# eMMC.net
KiCad netlist of a schematic drawn in Altium Designer
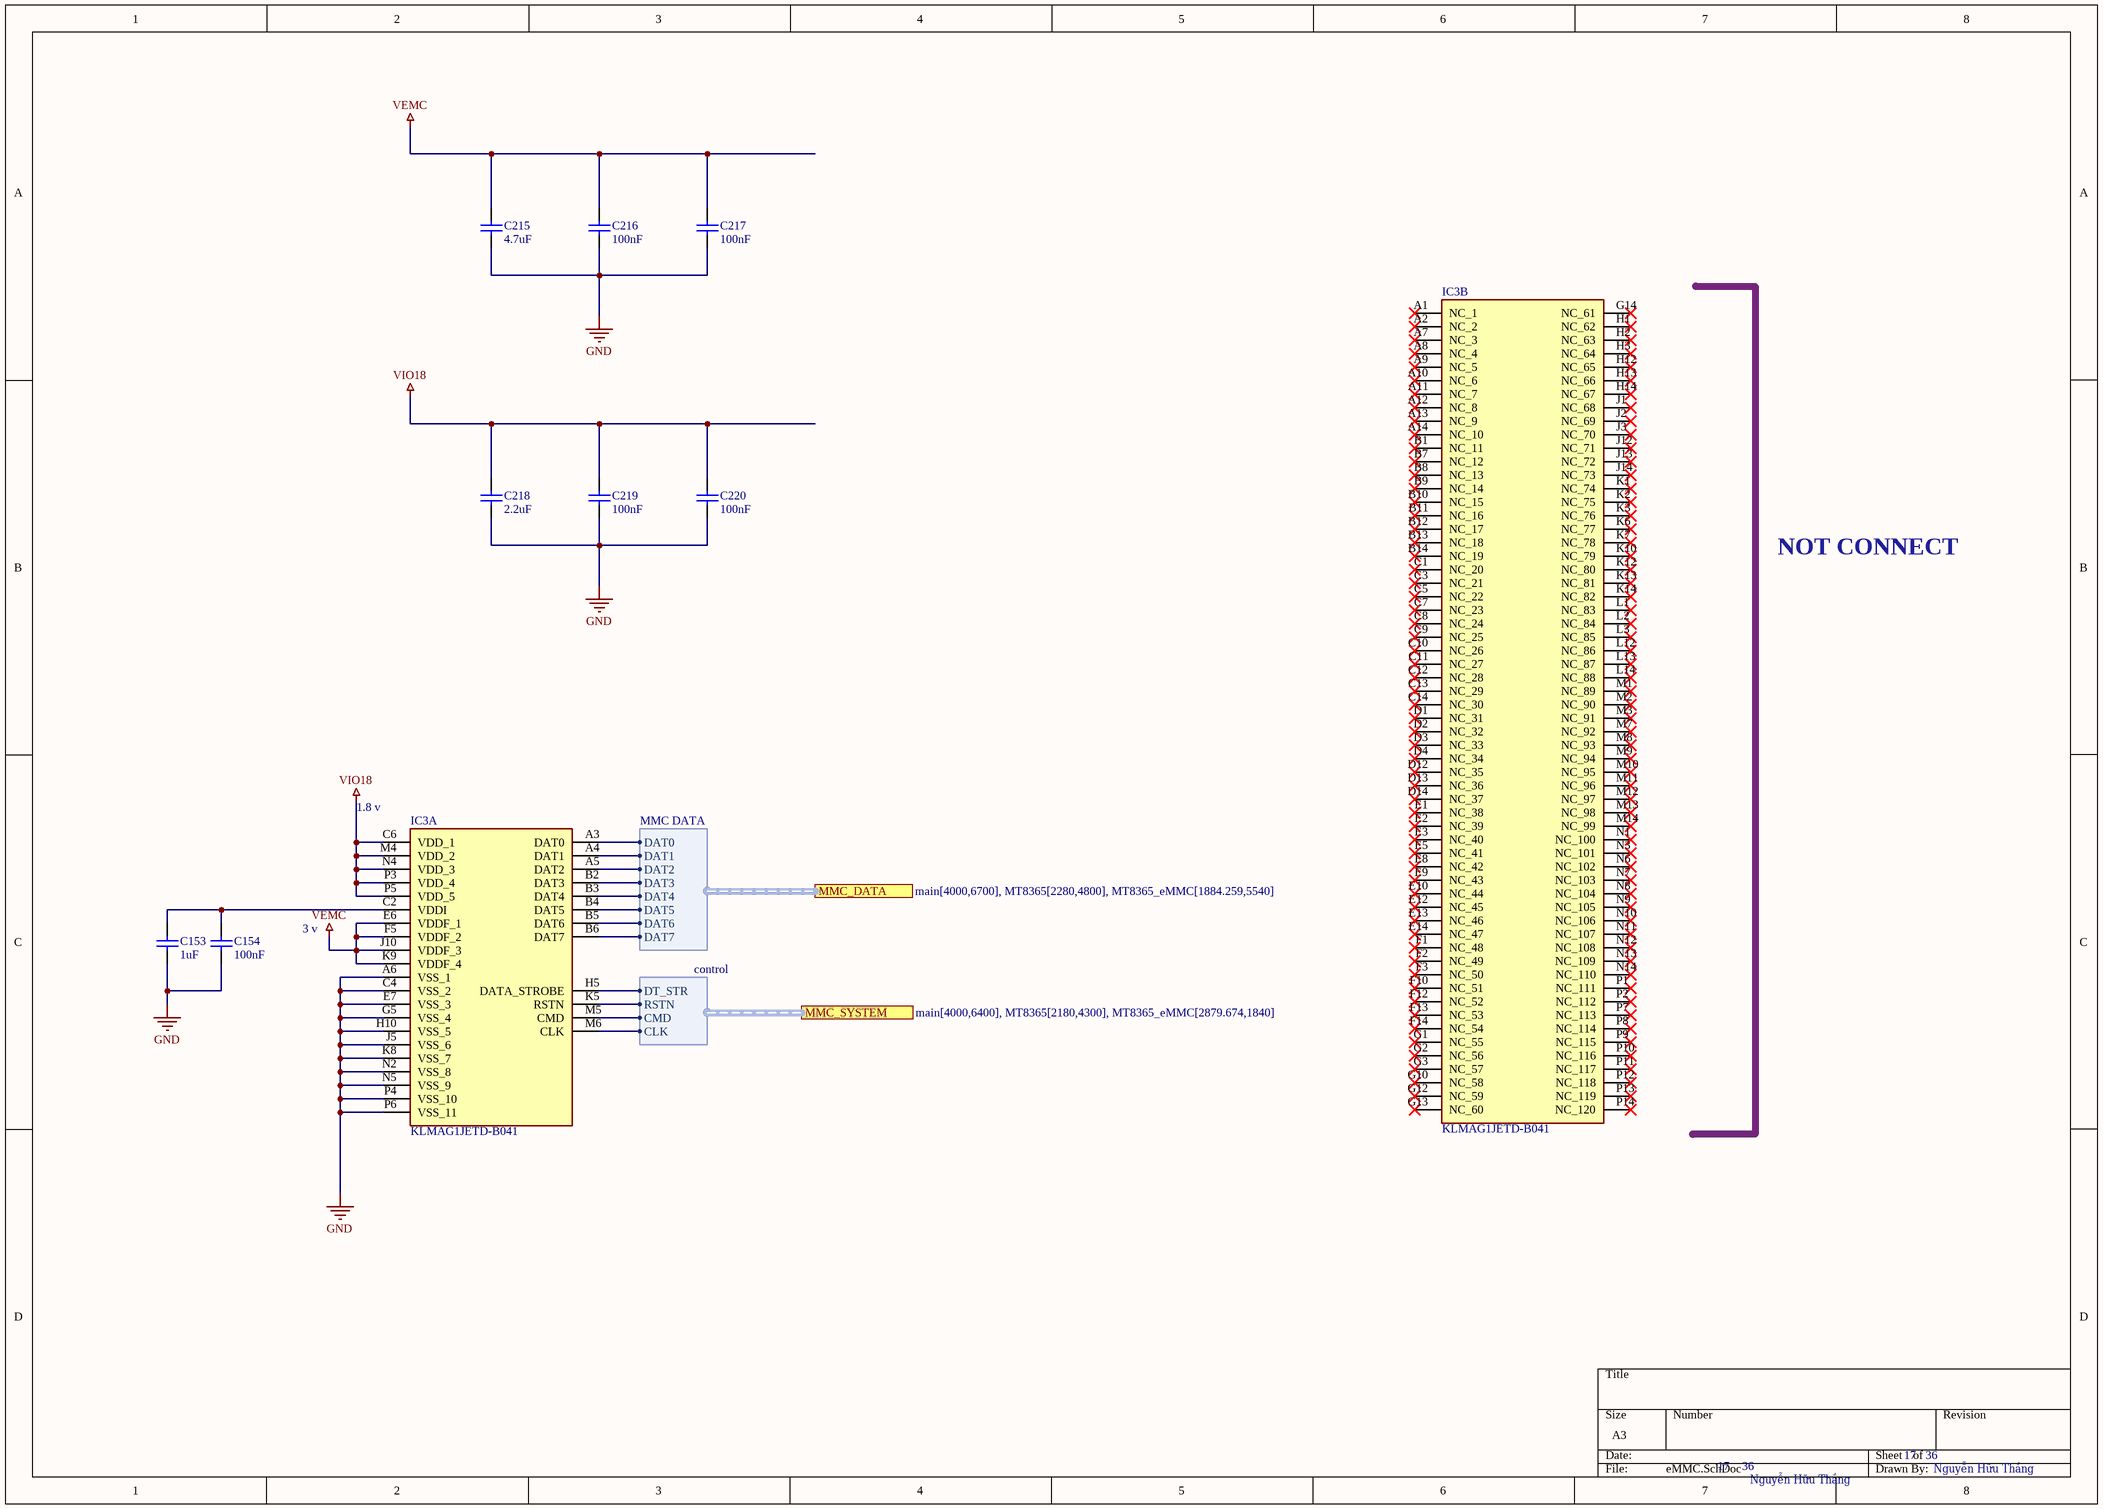
[diagram p0: eMMC.SchDoc]

(export (version "E")
  (design (tool "Eeschema 10.0.6"))
  (components
    (comp (ref "C153")
      (value "1uF")
      (footprint "C0805")
      (fields (field (name "Comment") "C0805"))
      (libsource (lib "kit") (part "C0805"))
    )
    (comp (ref "C154")
      (value "100nF")
      (footprint "C0603")
      (fields (field (name "Comment") "C0603"))
      (libsource (lib "kit") (part "C0603"))
    )
    (comp (ref "C215")
      (value "4.7uF")
      (footprint "C0805")
      (fields (field (name "Comment") "C0805"))
      (libsource (lib "kit") (part "C0805"))
    )
    (comp (ref "C216")
      (value "100nF")
      (footprint "C0603")
      (fields (field (name "Comment") "C0603"))
      (libsource (lib "kit") (part "C0603"))
    )
    (comp (ref "C217")
      (value "100nF")
      (footprint "C0603")
      (fields (field (name "Comment") "C0603"))
      (libsource (lib "kit") (part "C0603"))
    )
    (comp (ref "C218")
      (value "2.2uF")
      (footprint "C0805")
      (fields (field (name "Comment") "C0805"))
      (libsource (lib "kit") (part "C0805"))
    )
    (comp (ref "C219")
      (value "100nF")
      (footprint "C0603")
      (fields (field (name "Comment") "C0603"))
      (libsource (lib "kit") (part "C0603"))
    )
    (comp (ref "C220")
      (value "100nF")
      (footprint "C0603")
      (fields (field (name "Comment") "C0603"))
      (libsource (lib "kit") (part "C0603"))
    )
    (comp (ref "IC3")
      (value "KLMAG1JETD-B041")
      (footprint "BGA153C50P14X14_1150X1300X80")
      (description "Integrated Circuit")
      (libsource (lib "") (part "KLMAG1JETD-B041_1"))
    )
  )
  (nets
    (net (code "4") (name "/CLK") (class "Default")
      (node (ref "IC3") (pin "M6") (pinfunction "CLK_M6") (pintype "passive"))
    )
    (net (code "5") (name "/CMD") (class "Default")
      (node (ref "IC3") (pin "M5") (pinfunction "CMD_M5") (pintype "passive"))
    )
    (net (code "6") (name "/DAT0") (class "Default")
      (node (ref "IC3") (pin "A3") (pinfunction "DAT0_A3") (pintype "passive"))
    )
    (net (code "7") (name "/DAT1") (class "Default")
      (node (ref "IC3") (pin "A4") (pinfunction "DAT1_A4") (pintype "passive"))
    )
    (net (code "8") (name "/DAT2") (class "Default")
      (node (ref "IC3") (pin "A5") (pinfunction "DAT2_A5") (pintype "passive"))
    )
    (net (code "9") (name "/DAT3") (class "Default")
      (node (ref "IC3") (pin "B2") (pinfunction "DAT3_B2") (pintype "passive"))
    )
    (net (code "10") (name "/DAT4") (class "Default")
      (node (ref "IC3") (pin "B3") (pinfunction "DAT4_B3") (pintype "passive"))
    )
    (net (code "11") (name "/DAT5") (class "Default")
      (node (ref "IC3") (pin "B4") (pinfunction "DAT5_B4") (pintype "passive"))
    )
    (net (code "12") (name "/DAT6") (class "Default")
      (node (ref "IC3") (pin "B5") (pinfunction "DAT6_B5") (pintype "passive"))
    )
    (net (code "13") (name "/DAT7") (class "Default")
      (node (ref "IC3") (pin "B6") (pinfunction "DAT7_B6") (pintype "passive"))
    )
    (net (code "14") (name "/DT_STR") (class "Default")
      (node (ref "IC3") (pin "H5") (pinfunction "DATA_STROBE_H5") (pintype "passive"))
    )
    (net (code "15") (name "/RSTN") (class "Default")
      (node (ref "IC3") (pin "K5") (pinfunction "RSTN_K5") (pintype "passive"))
    )
    (net (code "18") (name "GND") (class "Default")
      (node (ref "C153") (pin "1") (pinfunction "1_1") (pintype "passive"))
      (node (ref "C154") (pin "1") (pinfunction "1_1") (pintype "passive"))
      (node (ref "C215") (pin "1") (pinfunction "1_1") (pintype "passive"))
      (node (ref "C216") (pin "1") (pinfunction "1_1") (pintype "passive"))
      (node (ref "C217") (pin "1") (pinfunction "1_1") (pintype "passive"))
      (node (ref "C218") (pin "1") (pinfunction "1_1") (pintype "passive"))
      (node (ref "C219") (pin "1") (pinfunction "1_1") (pintype "passive"))
      (node (ref "C220") (pin "1") (pinfunction "1_1") (pintype "passive"))
      (node (ref "IC3") (pin "A6") (pinfunction "VSS_1_A6") (pintype "passive"))
      (node (ref "IC3") (pin "C4") (pinfunction "VSS_2_C4") (pintype "passive"))
      (node (ref "IC3") (pin "E7") (pinfunction "VSS_3_E7") (pintype "passive"))
      (node (ref "IC3") (pin "G5") (pinfunction "VSS_4_G5") (pintype "passive"))
      (node (ref "IC3") (pin "H10") (pinfunction "VSS_5_H10") (pintype "passive"))
      (node (ref "IC3") (pin "J5") (pinfunction "VSS_6_J5") (pintype "passive"))
      (node (ref "IC3") (pin "K8") (pinfunction "VSS_7_K8") (pintype "passive"))
      (node (ref "IC3") (pin "N2") (pinfunction "VSS_8_N2") (pintype "passive"))
      (node (ref "IC3") (pin "N5") (pinfunction "VSS_9_N5") (pintype "passive"))
      (node (ref "IC3") (pin "P4") (pinfunction "VSS_10_P4") (pintype "passive"))
      (node (ref "IC3") (pin "P6") (pinfunction "VSS_11_P6") (pintype "passive"))
    )
    (net (code "19") (name "Net-(IC3A-VDDI)") (class "Default")
      (node (ref "C153") (pin "2") (pinfunction "2_2") (pintype "passive"))
      (node (ref "C154") (pin "2") (pinfunction "2_2") (pintype "passive"))
      (node (ref "IC3") (pin "C2") (pinfunction "VDDI_C2") (pintype "passive"))
    )
    (net (code "20") (name "VEMC") (class "Default")
      (node (ref "C215") (pin "2") (pinfunction "2_2") (pintype "passive"))
      (node (ref "C216") (pin "2") (pinfunction "2_2") (pintype "passive"))
      (node (ref "C217") (pin "2") (pinfunction "2_2") (pintype "passive"))
      (node (ref "IC3") (pin "E6") (pinfunction "VDDF_1_E6") (pintype "passive"))
      (node (ref "IC3") (pin "F5") (pinfunction "VDDF_2_F5") (pintype "passive"))
      (node (ref "IC3") (pin "J10") (pinfunction "VDDF_3_J10") (pintype "passive"))
      (node (ref "IC3") (pin "K9") (pinfunction "VDDF_4_K9") (pintype "passive"))
    )
    (net (code "21") (name "VIO18") (class "Default")
      (node (ref "C218") (pin "2") (pinfunction "2_2") (pintype "passive"))
      (node (ref "C219") (pin "2") (pinfunction "2_2") (pintype "passive"))
      (node (ref "C220") (pin "2") (pinfunction "2_2") (pintype "passive"))
      (node (ref "IC3") (pin "C6") (pinfunction "VDD_1_C6") (pintype "passive"))
      (node (ref "IC3") (pin "M4") (pinfunction "VDD_2_M4") (pintype "passive"))
      (node (ref "IC3") (pin "N4") (pinfunction "VDD_3_N4") (pintype "passive"))
      (node (ref "IC3") (pin "P3") (pinfunction "VDD_4_P3") (pintype "passive"))
      (node (ref "IC3") (pin "P5") (pinfunction "VDD_5_P5") (pintype "passive"))
    )
    (net (code "22") (name "unconnected-(IC3B-NC_1-PadA1)") (class "Default")
      (node (ref "IC3") (pin "A1") (pinfunction "NC_1_A1") (pintype "passive+no_connect"))
    )
    (net (code "23") (name "unconnected-(IC3B-NC_2-PadA2)") (class "Default")
      (node (ref "IC3") (pin "A2") (pinfunction "NC_2_A2") (pintype "passive+no_connect"))
    )
    (net (code "24") (name "unconnected-(IC3B-NC_3-PadA7)") (class "Default")
      (node (ref "IC3") (pin "A7") (pinfunction "NC_3_A7") (pintype "passive+no_connect"))
    )
    (net (code "25") (name "unconnected-(IC3B-NC_4-PadA8)") (class "Default")
      (node (ref "IC3") (pin "A8") (pinfunction "NC_4_A8") (pintype "passive+no_connect"))
    )
    (net (code "26") (name "unconnected-(IC3B-NC_5-PadA9)") (class "Default")
      (node (ref "IC3") (pin "A9") (pinfunction "NC_5_A9") (pintype "passive+no_connect"))
    )
    (net (code "27") (name "unconnected-(IC3B-NC_6-PadA10)") (class "Default")
      (node (ref "IC3") (pin "A10") (pinfunction "NC_6_A10") (pintype "passive+no_connect"))
    )
    (net (code "28") (name "unconnected-(IC3B-NC_7-PadA11)") (class "Default")
      (node (ref "IC3") (pin "A11") (pinfunction "NC_7_A11") (pintype "passive+no_connect"))
    )
    (net (code "29") (name "unconnected-(IC3B-NC_8-PadA12)") (class "Default")
      (node (ref "IC3") (pin "A12") (pinfunction "NC_8_A12") (pintype "passive+no_connect"))
    )
    (net (code "30") (name "unconnected-(IC3B-NC_9-PadA13)") (class "Default")
      (node (ref "IC3") (pin "A13") (pinfunction "NC_9_A13") (pintype "passive+no_connect"))
    )
    (net (code "31") (name "unconnected-(IC3B-NC_10-PadA14)") (class "Default")
      (node (ref "IC3") (pin "A14") (pinfunction "NC_10_A14") (pintype "passive+no_connect"))
    )
    (net (code "32") (name "unconnected-(IC3B-NC_11-PadB1)") (class "Default")
      (node (ref "IC3") (pin "B1") (pinfunction "NC_11_B1") (pintype "passive+no_connect"))
    )
    (net (code "33") (name "unconnected-(IC3B-NC_12-PadB7)") (class "Default")
      (node (ref "IC3") (pin "B7") (pinfunction "NC_12_B7") (pintype "passive+no_connect"))
    )
    (net (code "34") (name "unconnected-(IC3B-NC_13-PadB8)") (class "Default")
      (node (ref "IC3") (pin "B8") (pinfunction "NC_13_B8") (pintype "passive+no_connect"))
    )
    (net (code "35") (name "unconnected-(IC3B-NC_14-PadB9)") (class "Default")
      (node (ref "IC3") (pin "B9") (pinfunction "NC_14_B9") (pintype "passive+no_connect"))
    )
    (net (code "36") (name "unconnected-(IC3B-NC_15-PadB10)") (class "Default")
      (node (ref "IC3") (pin "B10") (pinfunction "NC_15_B10") (pintype "passive+no_connect"))
    )
    (net (code "37") (name "unconnected-(IC3B-NC_16-PadB11)") (class "Default")
      (node (ref "IC3") (pin "B11") (pinfunction "NC_16_B11") (pintype "passive+no_connect"))
    )
    (net (code "38") (name "unconnected-(IC3B-NC_17-PadB12)") (class "Default")
      (node (ref "IC3") (pin "B12") (pinfunction "NC_17_B12") (pintype "passive+no_connect"))
    )
    (net (code "39") (name "unconnected-(IC3B-NC_18-PadB13)") (class "Default")
      (node (ref "IC3") (pin "B13") (pinfunction "NC_18_B13") (pintype "passive+no_connect"))
    )
    (net (code "40") (name "unconnected-(IC3B-NC_19-PadB14)") (class "Default")
      (node (ref "IC3") (pin "B14") (pinfunction "NC_19_B14") (pintype "passive+no_connect"))
    )
    (net (code "41") (name "unconnected-(IC3B-NC_20-PadC1)") (class "Default")
      (node (ref "IC3") (pin "C1") (pinfunction "NC_20_C1") (pintype "passive+no_connect"))
    )
    (net (code "42") (name "unconnected-(IC3B-NC_21-PadC3)") (class "Default")
      (node (ref "IC3") (pin "C3") (pinfunction "NC_21_C3") (pintype "passive+no_connect"))
    )
    (net (code "43") (name "unconnected-(IC3B-NC_22-PadC5)") (class "Default")
      (node (ref "IC3") (pin "C5") (pinfunction "NC_22_C5") (pintype "passive+no_connect"))
    )
    (net (code "44") (name "unconnected-(IC3B-NC_23-PadC7)") (class "Default")
      (node (ref "IC3") (pin "C7") (pinfunction "NC_23_C7") (pintype "passive+no_connect"))
    )
    (net (code "45") (name "unconnected-(IC3B-NC_24-PadC8)") (class "Default")
      (node (ref "IC3") (pin "C8") (pinfunction "NC_24_C8") (pintype "passive+no_connect"))
    )
    (net (code "46") (name "unconnected-(IC3B-NC_25-PadC9)") (class "Default")
      (node (ref "IC3") (pin "C9") (pinfunction "NC_25_C9") (pintype "passive+no_connect"))
    )
    (net (code "47") (name "unconnected-(IC3B-NC_26-PadC10)") (class "Default")
      (node (ref "IC3") (pin "C10") (pinfunction "NC_26_C10") (pintype "passive+no_connect"))
    )
    (net (code "48") (name "unconnected-(IC3B-NC_27-PadC11)") (class "Default")
      (node (ref "IC3") (pin "C11") (pinfunction "NC_27_C11") (pintype "passive+no_connect"))
    )
    (net (code "49") (name "unconnected-(IC3B-NC_28-PadC12)") (class "Default")
      (node (ref "IC3") (pin "C12") (pinfunction "NC_28_C12") (pintype "passive+no_connect"))
    )
    (net (code "50") (name "unconnected-(IC3B-NC_29-PadC13)") (class "Default")
      (node (ref "IC3") (pin "C13") (pinfunction "NC_29_C13") (pintype "passive+no_connect"))
    )
    (net (code "51") (name "unconnected-(IC3B-NC_30-PadC14)") (class "Default")
      (node (ref "IC3") (pin "C14") (pinfunction "NC_30_C14") (pintype "passive+no_connect"))
    )
    (net (code "52") (name "unconnected-(IC3B-NC_31-PadD1)") (class "Default")
      (node (ref "IC3") (pin "D1") (pinfunction "NC_31_D1") (pintype "passive+no_connect"))
    )
    (net (code "53") (name "unconnected-(IC3B-NC_32-PadD2)") (class "Default")
      (node (ref "IC3") (pin "D2") (pinfunction "NC_32_D2") (pintype "passive+no_connect"))
    )
    (net (code "54") (name "unconnected-(IC3B-NC_33-PadD3)") (class "Default")
      (node (ref "IC3") (pin "D3") (pinfunction "NC_33_D3") (pintype "passive+no_connect"))
    )
    (net (code "55") (name "unconnected-(IC3B-NC_34-PadD4)") (class "Default")
      (node (ref "IC3") (pin "D4") (pinfunction "NC_34_D4") (pintype "passive+no_connect"))
    )
    (net (code "56") (name "unconnected-(IC3B-NC_35-PadD12)") (class "Default")
      (node (ref "IC3") (pin "D12") (pinfunction "NC_35_D12") (pintype "passive+no_connect"))
    )
    (net (code "57") (name "unconnected-(IC3B-NC_36-PadD13)") (class "Default")
      (node (ref "IC3") (pin "D13") (pinfunction "NC_36_D13") (pintype "passive+no_connect"))
    )
    (net (code "58") (name "unconnected-(IC3B-NC_37-PadD14)") (class "Default")
      (node (ref "IC3") (pin "D14") (pinfunction "NC_37_D14") (pintype "passive+no_connect"))
    )
    (net (code "59") (name "unconnected-(IC3B-NC_38-PadE1)") (class "Default")
      (node (ref "IC3") (pin "E1") (pinfunction "NC_38_E1") (pintype "passive+no_connect"))
    )
    (net (code "60") (name "unconnected-(IC3B-NC_39-PadE2)") (class "Default")
      (node (ref "IC3") (pin "E2") (pinfunction "NC_39_E2") (pintype "passive+no_connect"))
    )
    (net (code "61") (name "unconnected-(IC3B-NC_40-PadE3)") (class "Default")
      (node (ref "IC3") (pin "E3") (pinfunction "NC_40_E3") (pintype "passive+no_connect"))
    )
    (net (code "62") (name "unconnected-(IC3B-NC_41-PadE5)") (class "Default")
      (node (ref "IC3") (pin "E5") (pinfunction "NC_41_E5") (pintype "passive+no_connect"))
    )
    (net (code "63") (name "unconnected-(IC3B-NC_42-PadE8)") (class "Default")
      (node (ref "IC3") (pin "E8") (pinfunction "NC_42_E8") (pintype "passive+no_connect"))
    )
    (net (code "64") (name "unconnected-(IC3B-NC_43-PadE9)") (class "Default")
      (node (ref "IC3") (pin "E9") (pinfunction "NC_43_E9") (pintype "passive+no_connect"))
    )
    (net (code "65") (name "unconnected-(IC3B-NC_44-PadE10)") (class "Default")
      (node (ref "IC3") (pin "E10") (pinfunction "NC_44_E10") (pintype "passive+no_connect"))
    )
    (net (code "66") (name "unconnected-(IC3B-NC_45-PadE12)") (class "Default")
      (node (ref "IC3") (pin "E12") (pinfunction "NC_45_E12") (pintype "passive+no_connect"))
    )
    (net (code "67") (name "unconnected-(IC3B-NC_46-PadE13)") (class "Default")
      (node (ref "IC3") (pin "E13") (pinfunction "NC_46_E13") (pintype "passive+no_connect"))
    )
    (net (code "68") (name "unconnected-(IC3B-NC_47-PadE14)") (class "Default")
      (node (ref "IC3") (pin "E14") (pinfunction "NC_47_E14") (pintype "passive+no_connect"))
    )
    (net (code "69") (name "unconnected-(IC3B-NC_48-PadF1)") (class "Default")
      (node (ref "IC3") (pin "F1") (pinfunction "NC_48_F1") (pintype "passive+no_connect"))
    )
    (net (code "70") (name "unconnected-(IC3B-NC_49-PadF2)") (class "Default")
      (node (ref "IC3") (pin "F2") (pinfunction "NC_49_F2") (pintype "passive+no_connect"))
    )
    (net (code "71") (name "unconnected-(IC3B-NC_50-PadF3)") (class "Default")
      (node (ref "IC3") (pin "F3") (pinfunction "NC_50_F3") (pintype "passive+no_connect"))
    )
    (net (code "72") (name "unconnected-(IC3B-NC_51-PadF10)") (class "Default")
      (node (ref "IC3") (pin "F10") (pinfunction "NC_51_F10") (pintype "passive+no_connect"))
    )
    (net (code "73") (name "unconnected-(IC3B-NC_52-PadF12)") (class "Default")
      (node (ref "IC3") (pin "F12") (pinfunction "NC_52_F12") (pintype "passive+no_connect"))
    )
    (net (code "74") (name "unconnected-(IC3B-NC_53-PadF13)") (class "Default")
      (node (ref "IC3") (pin "F13") (pinfunction "NC_53_F13") (pintype "passive+no_connect"))
    )
    (net (code "75") (name "unconnected-(IC3B-NC_54-PadF14)") (class "Default")
      (node (ref "IC3") (pin "F14") (pinfunction "NC_54_F14") (pintype "passive+no_connect"))
    )
    (net (code "76") (name "unconnected-(IC3B-NC_55-PadG1)") (class "Default")
      (node (ref "IC3") (pin "G1") (pinfunction "NC_55_G1") (pintype "passive+no_connect"))
    )
    (net (code "77") (name "unconnected-(IC3B-NC_56-PadG2)") (class "Default")
      (node (ref "IC3") (pin "G2") (pinfunction "NC_56_G2") (pintype "passive+no_connect"))
    )
    (net (code "78") (name "unconnected-(IC3B-NC_57-PadG3)") (class "Default")
      (node (ref "IC3") (pin "G3") (pinfunction "NC_57_G3") (pintype "passive+no_connect"))
    )
    (net (code "79") (name "unconnected-(IC3B-NC_58-PadG10)") (class "Default")
      (node (ref "IC3") (pin "G10") (pinfunction "NC_58_G10") (pintype "passive+no_connect"))
    )
    (net (code "80") (name "unconnected-(IC3B-NC_59-PadG12)") (class "Default")
      (node (ref "IC3") (pin "G12") (pinfunction "NC_59_G12") (pintype "passive+no_connect"))
    )
    (net (code "81") (name "unconnected-(IC3B-NC_60-PadG13)") (class "Default")
      (node (ref "IC3") (pin "G13") (pinfunction "NC_60_G13") (pintype "passive+no_connect"))
    )
    (net (code "82") (name "unconnected-(IC3B-NC_61-PadG14)") (class "Default")
      (node (ref "IC3") (pin "G14") (pinfunction "NC_61_G14") (pintype "passive+no_connect"))
    )
    (net (code "83") (name "unconnected-(IC3B-NC_62-PadH1)") (class "Default")
      (node (ref "IC3") (pin "H1") (pinfunction "NC_62_H1") (pintype "passive+no_connect"))
    )
    (net (code "84") (name "unconnected-(IC3B-NC_63-PadH2)") (class "Default")
      (node (ref "IC3") (pin "H2") (pinfunction "NC_63_H2") (pintype "passive+no_connect"))
    )
    (net (code "85") (name "unconnected-(IC3B-NC_64-PadH3)") (class "Default")
      (node (ref "IC3") (pin "H3") (pinfunction "NC_64_H3") (pintype "passive+no_connect"))
    )
    (net (code "86") (name "unconnected-(IC3B-NC_65-PadH12)") (class "Default")
      (node (ref "IC3") (pin "H12") (pinfunction "NC_65_H12") (pintype "passive+no_connect"))
    )
    (net (code "87") (name "unconnected-(IC3B-NC_66-PadH13)") (class "Default")
      (node (ref "IC3") (pin "H13") (pinfunction "NC_66_H13") (pintype "passive+no_connect"))
    )
    (net (code "88") (name "unconnected-(IC3B-NC_67-PadH14)") (class "Default")
      (node (ref "IC3") (pin "H14") (pinfunction "NC_67_H14") (pintype "passive+no_connect"))
    )
    (net (code "89") (name "unconnected-(IC3B-NC_68-PadJ1)") (class "Default")
      (node (ref "IC3") (pin "J1") (pinfunction "NC_68_J1") (pintype "passive+no_connect"))
    )
    (net (code "90") (name "unconnected-(IC3B-NC_69-PadJ2)") (class "Default")
      (node (ref "IC3") (pin "J2") (pinfunction "NC_69_J2") (pintype "passive+no_connect"))
    )
    (net (code "91") (name "unconnected-(IC3B-NC_70-PadJ3)") (class "Default")
      (node (ref "IC3") (pin "J3") (pinfunction "NC_70_J3") (pintype "passive+no_connect"))
    )
    (net (code "92") (name "unconnected-(IC3B-NC_71-PadJ12)") (class "Default")
      (node (ref "IC3") (pin "J12") (pinfunction "NC_71_J12") (pintype "passive+no_connect"))
    )
    (net (code "93") (name "unconnected-(IC3B-NC_72-PadJ13)") (class "Default")
      (node (ref "IC3") (pin "J13") (pinfunction "NC_72_J13") (pintype "passive+no_connect"))
    )
    (net (code "94") (name "unconnected-(IC3B-NC_73-PadJ14)") (class "Default")
      (node (ref "IC3") (pin "J14") (pinfunction "NC_73_J14") (pintype "passive+no_connect"))
    )
    (net (code "95") (name "unconnected-(IC3B-NC_74-PadK1)") (class "Default")
      (node (ref "IC3") (pin "K1") (pinfunction "NC_74_K1") (pintype "passive+no_connect"))
    )
    (net (code "96") (name "unconnected-(IC3B-NC_75-PadK2)") (class "Default")
      (node (ref "IC3") (pin "K2") (pinfunction "NC_75_K2") (pintype "passive+no_connect"))
    )
    (net (code "97") (name "unconnected-(IC3B-NC_76-PadK3)") (class "Default")
      (node (ref "IC3") (pin "K3") (pinfunction "NC_76_K3") (pintype "passive+no_connect"))
    )
    (net (code "98") (name "unconnected-(IC3B-NC_77-PadK6)") (class "Default")
      (node (ref "IC3") (pin "K6") (pinfunction "NC_77_K6") (pintype "passive+no_connect"))
    )
    (net (code "99") (name "unconnected-(IC3B-NC_78-PadK7)") (class "Default")
      (node (ref "IC3") (pin "K7") (pinfunction "NC_78_K7") (pintype "passive+no_connect"))
    )
    (net (code "100") (name "unconnected-(IC3B-NC_79-PadK10)") (class "Default")
      (node (ref "IC3") (pin "K10") (pinfunction "NC_79_K10") (pintype "passive+no_connect"))
    )
    (net (code "101") (name "unconnected-(IC3B-NC_80-PadK12)") (class "Default")
      (node (ref "IC3") (pin "K12") (pinfunction "NC_80_K12") (pintype "passive+no_connect"))
    )
    (net (code "102") (name "unconnected-(IC3B-NC_81-PadK13)") (class "Default")
      (node (ref "IC3") (pin "K13") (pinfunction "NC_81_K13") (pintype "passive+no_connect"))
    )
    (net (code "103") (name "unconnected-(IC3B-NC_82-PadK14)") (class "Default")
      (node (ref "IC3") (pin "K14") (pinfunction "NC_82_K14") (pintype "passive+no_connect"))
    )
    (net (code "104") (name "unconnected-(IC3B-NC_83-PadL1)") (class "Default")
      (node (ref "IC3") (pin "L1") (pinfunction "NC_83_L1") (pintype "passive+no_connect"))
    )
    (net (code "105") (name "unconnected-(IC3B-NC_84-PadL2)") (class "Default")
      (node (ref "IC3") (pin "L2") (pinfunction "NC_84_L2") (pintype "passive+no_connect"))
    )
    (net (code "106") (name "unconnected-(IC3B-NC_85-PadL3)") (class "Default")
      (node (ref "IC3") (pin "L3") (pinfunction "NC_85_L3") (pintype "passive+no_connect"))
    )
    (net (code "107") (name "unconnected-(IC3B-NC_86-PadL12)") (class "Default")
      (node (ref "IC3") (pin "L12") (pinfunction "NC_86_L12") (pintype "passive+no_connect"))
    )
    (net (code "108") (name "unconnected-(IC3B-NC_87-PadL13)") (class "Default")
      (node (ref "IC3") (pin "L13") (pinfunction "NC_87_L13") (pintype "passive+no_connect"))
    )
    (net (code "109") (name "unconnected-(IC3B-NC_88-PadL14)") (class "Default")
      (node (ref "IC3") (pin "L14") (pinfunction "NC_88_L14") (pintype "passive+no_connect"))
    )
    (net (code "110") (name "unconnected-(IC3B-NC_89-PadM1)") (class "Default")
      (node (ref "IC3") (pin "M1") (pinfunction "NC_89_M1") (pintype "passive+no_connect"))
    )
    (net (code "111") (name "unconnected-(IC3B-NC_90-PadM2)") (class "Default")
      (node (ref "IC3") (pin "M2") (pinfunction "NC_90_M2") (pintype "passive+no_connect"))
    )
    (net (code "112") (name "unconnected-(IC3B-NC_91-PadM3)") (class "Default")
      (node (ref "IC3") (pin "M3") (pinfunction "NC_91_M3") (pintype "passive+no_connect"))
    )
    (net (code "113") (name "unconnected-(IC3B-NC_92-PadM7)") (class "Default")
      (node (ref "IC3") (pin "M7") (pinfunction "NC_92_M7") (pintype "passive+no_connect"))
    )
    (net (code "114") (name "unconnected-(IC3B-NC_93-PadM8)") (class "Default")
      (node (ref "IC3") (pin "M8") (pinfunction "NC_93_M8") (pintype "passive+no_connect"))
    )
    (net (code "115") (name "unconnected-(IC3B-NC_94-PadM9)") (class "Default")
      (node (ref "IC3") (pin "M9") (pinfunction "NC_94_M9") (pintype "passive+no_connect"))
    )
    (net (code "116") (name "unconnected-(IC3B-NC_95-PadM10)") (class "Default")
      (node (ref "IC3") (pin "M10") (pinfunction "NC_95_M10") (pintype "passive+no_connect"))
    )
    (net (code "117") (name "unconnected-(IC3B-NC_96-PadM11)") (class "Default")
      (node (ref "IC3") (pin "M11") (pinfunction "NC_96_M11") (pintype "passive+no_connect"))
    )
    (net (code "118") (name "unconnected-(IC3B-NC_97-PadM12)") (class "Default")
      (node (ref "IC3") (pin "M12") (pinfunction "NC_97_M12") (pintype "passive+no_connect"))
    )
    (net (code "119") (name "unconnected-(IC3B-NC_98-PadM13)") (class "Default")
      (node (ref "IC3") (pin "M13") (pinfunction "NC_98_M13") (pintype "passive+no_connect"))
    )
    (net (code "120") (name "unconnected-(IC3B-NC_99-PadM14)") (class "Default")
      (node (ref "IC3") (pin "M14") (pinfunction "NC_99_M14") (pintype "passive+no_connect"))
    )
    (net (code "121") (name "unconnected-(IC3B-NC_100-PadN1)") (class "Default")
      (node (ref "IC3") (pin "N1") (pinfunction "NC_100_N1") (pintype "passive+no_connect"))
    )
    (net (code "122") (name "unconnected-(IC3B-NC_101-PadN3)") (class "Default")
      (node (ref "IC3") (pin "N3") (pinfunction "NC_101_N3") (pintype "passive+no_connect"))
    )
    (net (code "123") (name "unconnected-(IC3B-NC_102-PadN6)") (class "Default")
      (node (ref "IC3") (pin "N6") (pinfunction "NC_102_N6") (pintype "passive+no_connect"))
    )
    (net (code "124") (name "unconnected-(IC3B-NC_103-PadN7)") (class "Default")
      (node (ref "IC3") (pin "N7") (pinfunction "NC_103_N7") (pintype "passive+no_connect"))
    )
    (net (code "125") (name "unconnected-(IC3B-NC_104-PadN8)") (class "Default")
      (node (ref "IC3") (pin "N8") (pinfunction "NC_104_N8") (pintype "passive+no_connect"))
    )
    (net (code "126") (name "unconnected-(IC3B-NC_105-PadN9)") (class "Default")
      (node (ref "IC3") (pin "N9") (pinfunction "NC_105_N9") (pintype "passive+no_connect"))
    )
    (net (code "127") (name "unconnected-(IC3B-NC_106-PadN10)") (class "Default")
      (node (ref "IC3") (pin "N10") (pinfunction "NC_106_N10") (pintype "passive+no_connect"))
    )
    (net (code "128") (name "unconnected-(IC3B-NC_107-PadN11)") (class "Default")
      (node (ref "IC3") (pin "N11") (pinfunction "NC_107_N11") (pintype "passive+no_connect"))
    )
    (net (code "129") (name "unconnected-(IC3B-NC_108-PadN12)") (class "Default")
      (node (ref "IC3") (pin "N12") (pinfunction "NC_108_N12") (pintype "passive+no_connect"))
    )
    (net (code "130") (name "unconnected-(IC3B-NC_109-PadN13)") (class "Default")
      (node (ref "IC3") (pin "N13") (pinfunction "NC_109_N13") (pintype "passive+no_connect"))
    )
    (net (code "131") (name "unconnected-(IC3B-NC_110-PadN14)") (class "Default")
      (node (ref "IC3") (pin "N14") (pinfunction "NC_110_N14") (pintype "passive+no_connect"))
    )
    (net (code "132") (name "unconnected-(IC3B-NC_111-PadP1)") (class "Default")
      (node (ref "IC3") (pin "P1") (pinfunction "NC_111_P1") (pintype "passive+no_connect"))
    )
    (net (code "133") (name "unconnected-(IC3B-NC_112-PadP2)") (class "Default")
      (node (ref "IC3") (pin "P2") (pinfunction "NC_112_P2") (pintype "passive+no_connect"))
    )
    (net (code "134") (name "unconnected-(IC3B-NC_113-PadP7)") (class "Default")
      (node (ref "IC3") (pin "P7") (pinfunction "NC_113_P7") (pintype "passive+no_connect"))
    )
    (net (code "135") (name "unconnected-(IC3B-NC_114-PadP8)") (class "Default")
      (node (ref "IC3") (pin "P8") (pinfunction "NC_114_P8") (pintype "passive+no_connect"))
    )
    (net (code "136") (name "unconnected-(IC3B-NC_115-PadP9)") (class "Default")
      (node (ref "IC3") (pin "P9") (pinfunction "NC_115_P9") (pintype "passive+no_connect"))
    )
    (net (code "137") (name "unconnected-(IC3B-NC_116-PadP10)") (class "Default")
      (node (ref "IC3") (pin "P10") (pinfunction "NC_116_P10") (pintype "passive+no_connect"))
    )
    (net (code "138") (name "unconnected-(IC3B-NC_117-PadP11)") (class "Default")
      (node (ref "IC3") (pin "P11") (pinfunction "NC_117_P11") (pintype "passive+no_connect"))
    )
    (net (code "139") (name "unconnected-(IC3B-NC_118-PadP12)") (class "Default")
      (node (ref "IC3") (pin "P12") (pinfunction "NC_118_P12") (pintype "passive+no_connect"))
    )
    (net (code "140") (name "unconnected-(IC3B-NC_119-PadP13)") (class "Default")
      (node (ref "IC3") (pin "P13") (pinfunction "NC_119_P13") (pintype "passive+no_connect"))
    )
    (net (code "141") (name "unconnected-(IC3B-NC_120-PadP14)") (class "Default")
      (node (ref "IC3") (pin "P14") (pinfunction "NC_120_P14") (pintype "passive+no_connect"))
    )
  )
)
